# Smart_bot_V2_0.net
KiCad netlist of a schematic drawn in EAGLE
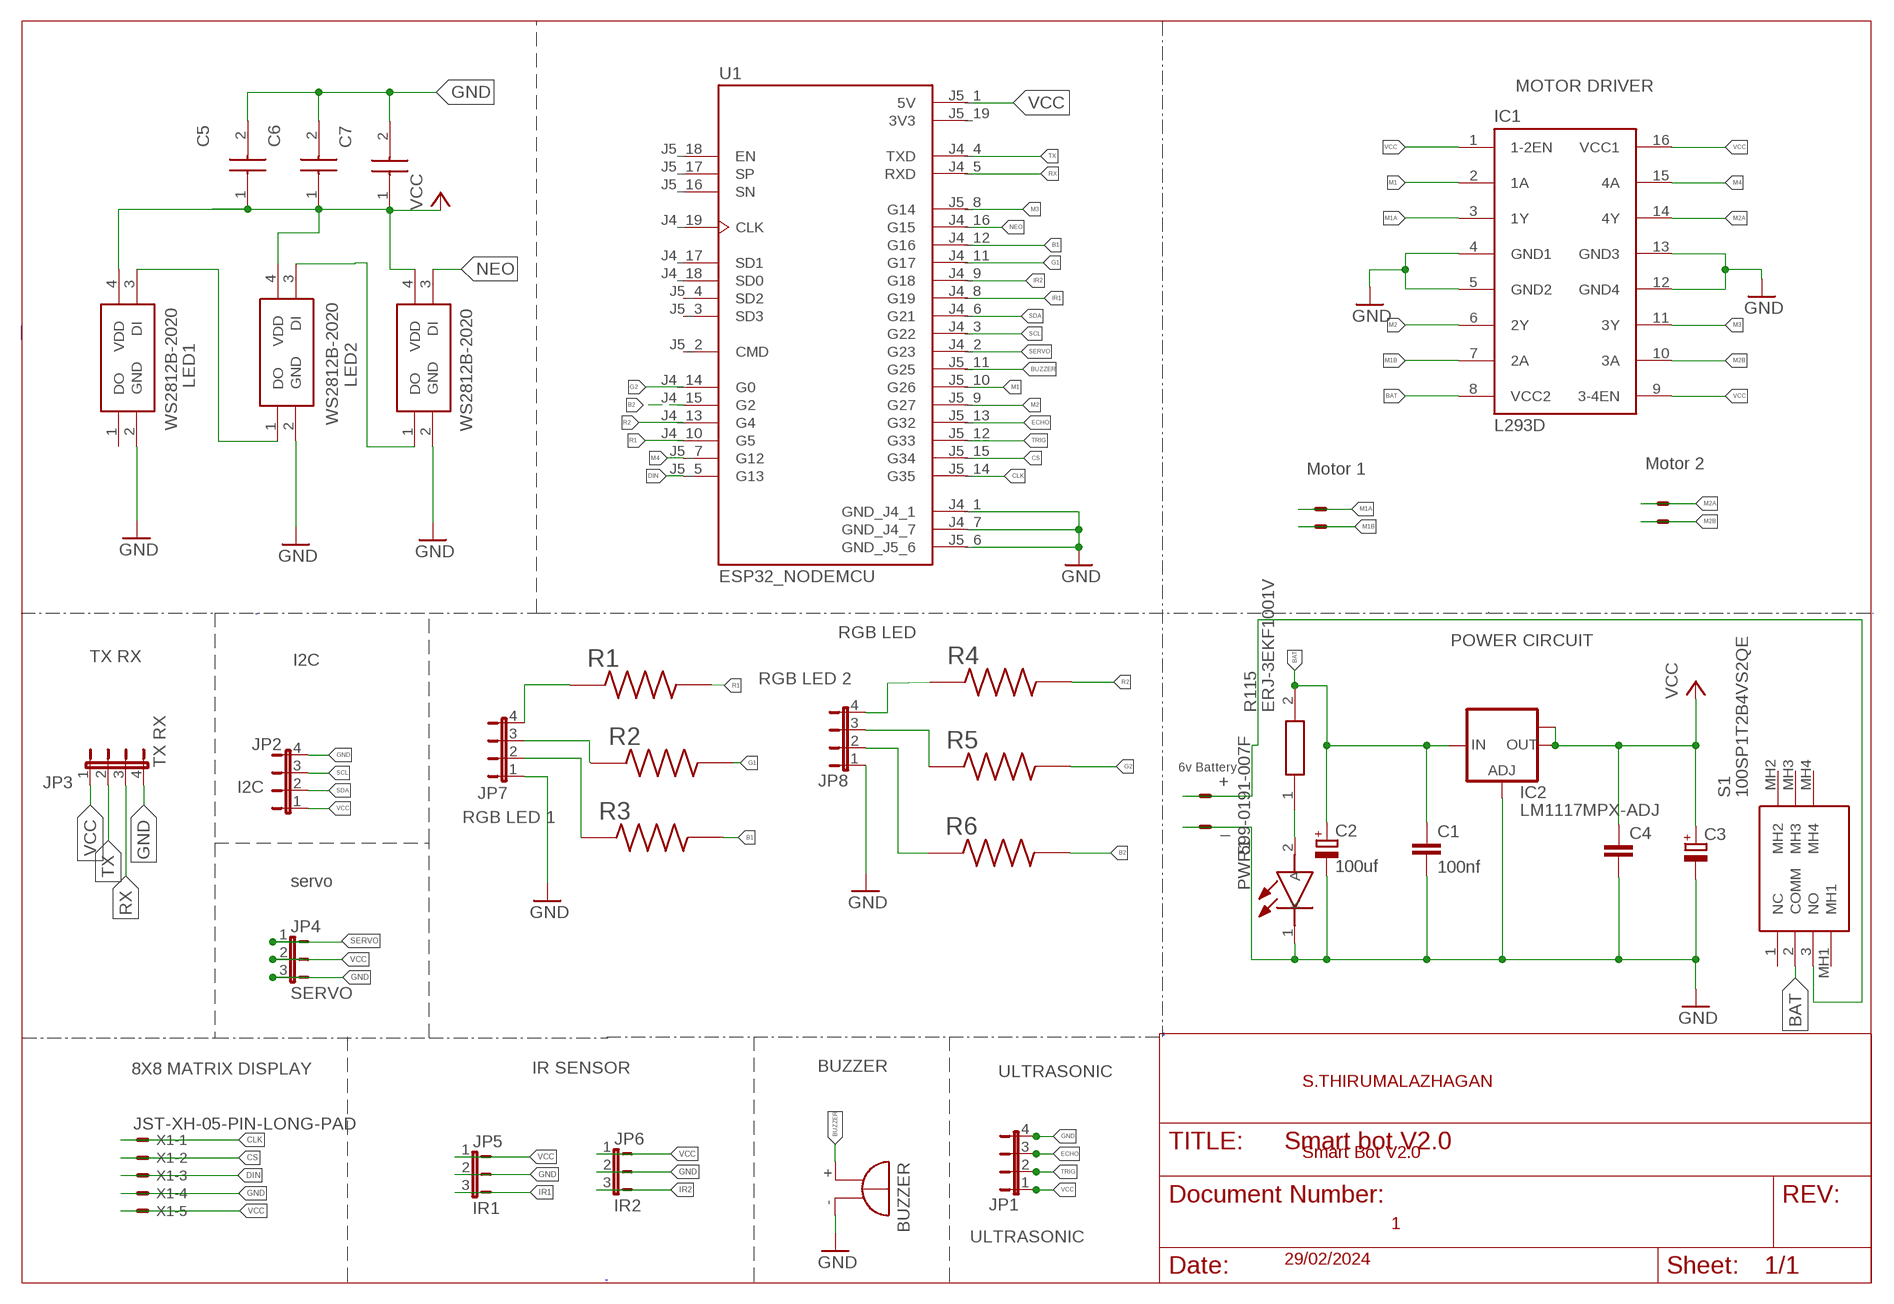
[diagram p0: schematic, sheet 1]

(export (version "E")
  (design (tool "Eeschema 10.0.6"))
  (components
    (comp (ref "6V")
      (value "JST-XH-02-PIN-LONG-PAD")
      (footprint "eagle-import:JST-XH-02-PACKAGE-LONG-PAD")
      (libsource (lib "eagle-import") (part "JST-XH-02-PIN-LONG-PAD"))
    )
    (comp (ref "BUZZER")
      (value "F/HMB")
      (footprint "eagle-import:F_HMB")
      (libsource (lib "eagle-import") (part "F/HMB"))
    )
    (comp (ref "C1")
      (value "100nf")
      (footprint "eagle-import:C1206")
      (libsource (lib "eagle-import") (part "C-EUC1206"))
    )
    (comp (ref "C2")
      (value "100uf")
      (footprint "eagle-import:SMC_B")
      (libsource (lib "eagle-import") (part "CPOL-EUSMCB"))
    )
    (comp (ref "C3")
      (value "CPOL-EUSMCB")
      (footprint "eagle-import:SMC_B")
      (libsource (lib "eagle-import") (part "CPOL-EUSMCB"))
    )
    (comp (ref "C4")
      (value "C-EUC1206")
      (footprint "eagle-import:C1206")
      (libsource (lib "eagle-import") (part "C-EUC1206"))
    )
    (comp (ref "C5")
      (value "C0805X102KMRECAUTO7210")
      (footprint "eagle-import:CAPC2012X98N")
      (fields (field (name "MOUSER_PART_NUMBER") "80-C0805X102KMREAULR"))
      (libsource (lib "eagle-import") (part "C0805X102KMRECAUTO7210"))
    )
    (comp (ref "C6")
      (value "C0805X102KMRECAUTO7210")
      (footprint "eagle-import:CAPC2012X98N")
      (fields (field (name "MOUSER_PART_NUMBER") "80-C0805X102KMREAULR"))
      (libsource (lib "eagle-import") (part "C0805X102KMRECAUTO7210"))
    )
    (comp (ref "C7")
      (value "C0805X102KMRECAUTO7210")
      (footprint "eagle-import:CAPC2012X98N")
      (fields (field (name "MOUSER_PART_NUMBER") "80-C0805X102KMREAULR"))
      (libsource (lib "eagle-import") (part "C0805X102KMRECAUTO7210"))
    )
    (comp (ref "IC1")
      (value "L293D")
      (footprint "eagle-import:DIL16")
      (libsource (lib "eagle-import") (part "L293D"))
    )
    (comp (ref "IC2")
      (value "LM1117MPX-ADJ")
      (footprint "eagle-import:SOT223")
      (libsource (lib "eagle-import") (part "LM1117MPX-ADJ"))
    )
    (comp (ref "JP1")
      (value "ULTRASONIC")
      (footprint "eagle-import:JP4")
      (libsource (lib "eagle-import") (part "JP4E"))
    )
    (comp (ref "JP2")
      (value "I2C")
      (footprint "eagle-import:JP4")
      (libsource (lib "eagle-import") (part "JP4E"))
    )
    (comp (ref "JP3")
      (value "TX RX")
      (footprint "eagle-import:JP4")
      (libsource (lib "eagle-import") (part "JP4E"))
    )
    (comp (ref "JP4")
      (value "SERVO")
      (footprint "eagle-import:JP2")
      (libsource (lib "eagle-import") (part "JP2E"))
    )
    (comp (ref "JP5")
      (value "IR1")
      (footprint "eagle-import:JP2")
      (libsource (lib "eagle-import") (part "JP2E"))
    )
    (comp (ref "JP6")
      (value "IR2")
      (footprint "eagle-import:JP2")
      (libsource (lib "eagle-import") (part "JP2E"))
    )
    (comp (ref "JP7")
      (value "RGB LED 1")
      (footprint "eagle-import:JP4")
      (libsource (lib "eagle-import") (part "JP4E"))
    )
    (comp (ref "JP8")
      (value "RGB LED 2")
      (footprint "eagle-import:JP4")
      (libsource (lib "eagle-import") (part "JP4E"))
    )
    (comp (ref "LED1")
      (value "WS2812B-2020")
      (footprint "eagle-import:WS2812B2020")
      (libsource (lib "eagle-import") (part "WS2812B-2020"))
    )
    (comp (ref "LED2")
      (value "WS2812B-2020")
      (footprint "eagle-import:WS2812B2020")
      (libsource (lib "eagle-import") (part "WS2812B-2020"))
    )
    (comp (ref "LED3")
      (value "WS2812B-2020")
      (footprint "eagle-import:WS2812B2020")
      (libsource (lib "eagle-import") (part "WS2812B-2020"))
    )
    (comp (ref "PWR1")
      (value "599-0191-007F")
      (footprint "eagle-import:LEDC2012X90N")
      (fields (field (name "MOUSER_PART_NUMBER") "645-599-0191-007F"))
      (libsource (lib "eagle-import") (part "599-0191-007F"))
    )
    (comp (ref "R1")
      (value "RR0306P-101-D")
      (footprint "eagle-import:RESC0603X26N")
      (fields (field (name "MF") "Susumu"))
      (libsource (lib "eagle-import") (part "RR0306P-101-D"))
    )
    (comp (ref "R2")
      (value "RR0306P-101-D")
      (footprint "eagle-import:RESC0603X26N")
      (fields (field (name "MF") "Susumu"))
      (libsource (lib "eagle-import") (part "RR0306P-101-D"))
    )
    (comp (ref "R3")
      (value "RR0306P-101-D")
      (footprint "eagle-import:RESC0603X26N")
      (fields (field (name "MF") "Susumu"))
      (libsource (lib "eagle-import") (part "RR0306P-101-D"))
    )
    (comp (ref "R4")
      (value "RR0306P-101-D")
      (footprint "eagle-import:RESC0603X26N")
      (fields (field (name "MF") "Susumu"))
      (libsource (lib "eagle-import") (part "RR0306P-101-D"))
    )
    (comp (ref "R5")
      (value "RR0306P-101-D")
      (footprint "eagle-import:RESC0603X26N")
      (fields (field (name "MF") "Susumu"))
      (libsource (lib "eagle-import") (part "RR0306P-101-D"))
    )
    (comp (ref "R6")
      (value "RR0306P-101-D")
      (footprint "eagle-import:RESC0603X26N")
      (fields (field (name "MF") "Susumu"))
      (libsource (lib "eagle-import") (part "RR0306P-101-D"))
    )
    (comp (ref "R115")
      (value "ERJ-3EKF1001V")
      (footprint "eagle-import:RESC1608X55N")
      (fields (field (name "MOUSER_PART_NUMBER") "667-ERJ-3EKF1001V"))
      (libsource (lib "eagle-import") (part "ERJ-3EKF1001V"))
    )
    (comp (ref "S1")
      (value "100SP1T2B4VS2QE")
      (footprint "eagle-import:100SP1T2B4VS2QE")
      (fields (field (name "MOUSER_PART_NUMBER") "612-100SP1T2B4VSQ"))
      (libsource (lib "eagle-import") (part "100SP1T2B4VS2QE"))
    )
    (comp (ref "U1")
      (value "ESP32_NODEMCU")
      (footprint "eagle-import:MODULE_ESP32_NODEMCU")
      (fields (field (name "MF") "AZ Delivery") (field (name "MP") "ESP32 NODEMCU"))
      (libsource (lib "eagle-import") (part "ESP32_NODEMCU"))
    )
    (comp (ref "X1")
      (value "JST-XH-05-PIN-LONG-PAD")
      (footprint "eagle-import:JST-XH-05-PACKAGE-LONG-PAD")
      (libsource (lib "eagle-import") (part "JST-XH-05-PIN-LONG-PAD"))
    )
    (comp (ref "X2")
      (value "JST-XH-02-PIN-LONG-PAD")
      (footprint "eagle-import:JST-XH-02-PACKAGE-LONG-PAD")
      (libsource (lib "eagle-import") (part "JST-XH-02-PIN-LONG-PAD"))
    )
    (comp (ref "X3")
      (value "JST-XH-02-PIN-LONG-PAD")
      (footprint "eagle-import:JST-XH-02-PACKAGE-LONG-PAD")
      (libsource (lib "eagle-import") (part "JST-XH-02-PIN-LONG-PAD"))
    )
  )
  (nets
    (net (code "1") (name "/3V3") (class "Default")
      (node (ref "U1") (pin "J5_19") (pinfunction "3V3_J5_19") (pintype "power_in"))
    )
    (net (code "2") (name "B1") (class "Default")
      (node (ref "R3") (pin "2") (pinfunction "2_2") (pintype "passive"))
      (node (ref "U1") (pin "J4_12") (pinfunction "G16_J4_12") (pintype "bidirectional"))
    )
    (net (code "3") (name "B2") (class "Default")
      (node (ref "R6") (pin "2") (pinfunction "2_2") (pintype "passive"))
      (node (ref "U1") (pin "J4_15") (pinfunction "G2_J4_15") (pintype "bidirectional"))
    )
    (net (code "4") (name "BAT") (class "Default")
      (node (ref "C1") (pin "1") (pinfunction "1_1") (pintype "passive"))
      (node (ref "C2") (pin "+") (pinfunction "+_+") (pintype "passive"))
      (node (ref "IC1") (pin "8") (pinfunction "VCC2_8") (pintype "power_in"))
      (node (ref "IC2") (pin "3") (pinfunction "IN_3") (pintype "input"))
      (node (ref "R115") (pin "2") (pinfunction "2_2") (pintype "bidirectional"))
      (node (ref "S1") (pin "2") (pinfunction "COMM_2") (pintype "bidirectional"))
    )
    (net (code "5") (name "BUZZER") (class "Default")
      (node (ref "BUZZER") (pin "+") (pinfunction "+_+") (pintype "passive"))
      (node (ref "U1") (pin "J5_11") (pinfunction "G25_J5_11") (pintype "bidirectional"))
    )
    (net (code "6") (name "CLK") (class "Default")
      (node (ref "U1") (pin "J5_14") (pinfunction "G35_J5_14") (pintype "bidirectional"))
      (node (ref "X1") (pin "1") (pinfunction "S_1") (pintype "passive"))
    )
    (net (code "7") (name "CS") (class "Default")
      (node (ref "U1") (pin "J5_15") (pinfunction "G34_J5_15") (pintype "bidirectional"))
      (node (ref "X1") (pin "2") (pinfunction "S_2") (pintype "passive"))
    )
    (net (code "8") (name "DIN") (class "Default")
      (node (ref "U1") (pin "J5_5") (pinfunction "G13_J5_5") (pintype "bidirectional"))
      (node (ref "X1") (pin "3") (pinfunction "S_3") (pintype "passive"))
    )
    (net (code "9") (name "ECHO") (class "Default")
      (node (ref "JP1") (pin "3") (pinfunction "3_3") (pintype "passive"))
      (node (ref "U1") (pin "J5_13") (pinfunction "G32_J5_13") (pintype "bidirectional"))
    )
    (net (code "10") (name "G1") (class "Default")
      (node (ref "R2") (pin "2") (pinfunction "2_2") (pintype "passive"))
      (node (ref "U1") (pin "J4_11") (pinfunction "G17_J4_11") (pintype "bidirectional"))
    )
    (net (code "11") (name "G2") (class "Default")
      (node (ref "R5") (pin "2") (pinfunction "2_2") (pintype "passive"))
      (node (ref "U1") (pin "J4_14") (pinfunction "G0_J4_14") (pintype "bidirectional"))
    )
    (net (code "12") (name "GND") (class "Default")
      (node (ref "6V") (pin "2") (pinfunction "S_2") (pintype "passive"))
      (node (ref "BUZZER") (pin "-") (pinfunction "-_-") (pintype "passive"))
      (node (ref "C1") (pin "2") (pinfunction "2_2") (pintype "passive"))
      (node (ref "C2") (pin "-") (pinfunction "-_-") (pintype "passive"))
      (node (ref "C3") (pin "-") (pinfunction "-_-") (pintype "passive"))
      (node (ref "C4") (pin "2") (pinfunction "2_2") (pintype "passive"))
      (node (ref "C5") (pin "2") (pinfunction "2_2") (pintype "bidirectional"))
      (node (ref "C6") (pin "2") (pinfunction "2_2") (pintype "bidirectional"))
      (node (ref "C7") (pin "2") (pinfunction "2_2") (pintype "bidirectional"))
      (node (ref "IC1") (pin "12") (pinfunction "GND4_12") (pintype "power_in"))
      (node (ref "IC1") (pin "13") (pinfunction "GND3_13") (pintype "power_in"))
      (node (ref "IC1") (pin "4") (pinfunction "GND1_4") (pintype "power_in"))
      (node (ref "IC1") (pin "5") (pinfunction "GND2_5") (pintype "power_in"))
      (node (ref "IC2") (pin "1") (pinfunction "ADJ_1") (pintype "input"))
      (node (ref "JP1") (pin "4") (pinfunction "4_4") (pintype "passive"))
      (node (ref "JP2") (pin "4") (pinfunction "4_4") (pintype "passive"))
      (node (ref "JP3") (pin "4") (pinfunction "4_4") (pintype "passive"))
      (node (ref "JP4") (pin "3") (pinfunction "3_3") (pintype "passive"))
      (node (ref "JP5") (pin "2") (pinfunction "2_2") (pintype "passive"))
      (node (ref "JP6") (pin "2") (pinfunction "2_2") (pintype "passive"))
      (node (ref "JP7") (pin "1") (pinfunction "1_1") (pintype "passive"))
      (node (ref "JP8") (pin "1") (pinfunction "1_1") (pintype "passive"))
      (node (ref "LED1") (pin "2") (pinfunction "GND_2") (pintype "bidirectional"))
      (node (ref "LED2") (pin "2") (pinfunction "GND_2") (pintype "bidirectional"))
      (node (ref "LED3") (pin "2") (pinfunction "GND_2") (pintype "bidirectional"))
      (node (ref "PWR1") (pin "1") (pinfunction "K_1") (pintype "bidirectional"))
      (node (ref "U1") (pin "J4_1") (pinfunction "GND_J4_1_J4_1") (pintype "power_in"))
      (node (ref "U1") (pin "J4_7") (pinfunction "GND_J4_7_J4_7") (pintype "power_in"))
      (node (ref "U1") (pin "J5_6") (pinfunction "GND_J5_6_J5_6") (pintype "power_in"))
      (node (ref "X1") (pin "4") (pinfunction "S_4") (pintype "passive"))
    )
    (net (code "13") (name "IR1") (class "Default")
      (node (ref "JP5") (pin "3") (pinfunction "3_3") (pintype "passive"))
      (node (ref "U1") (pin "J4_8") (pinfunction "G19_J4_8") (pintype "bidirectional"))
    )
    (net (code "14") (name "IR2") (class "Default")
      (node (ref "JP6") (pin "3") (pinfunction "3_3") (pintype "passive"))
      (node (ref "U1") (pin "J4_9") (pinfunction "G18_J4_9") (pintype "bidirectional"))
    )
    (net (code "15") (name "M1") (class "Default")
      (node (ref "IC1") (pin "2") (pinfunction "1A_2") (pintype "input"))
      (node (ref "U1") (pin "J5_10") (pinfunction "G26_J5_10") (pintype "bidirectional"))
    )
    (net (code "16") (name "M1A") (class "Default")
      (node (ref "IC1") (pin "3") (pinfunction "1Y_3") (pintype "output"))
      (node (ref "X2") (pin "1") (pinfunction "S_1") (pintype "passive"))
    )
    (net (code "17") (name "M1B") (class "Default")
      (node (ref "IC1") (pin "7") (pinfunction "2A_7") (pintype "input"))
      (node (ref "X2") (pin "2") (pinfunction "S_2") (pintype "passive"))
    )
    (net (code "18") (name "M2") (class "Default")
      (node (ref "IC1") (pin "6") (pinfunction "2Y_6") (pintype "output"))
      (node (ref "U1") (pin "J5_9") (pinfunction "G27_J5_9") (pintype "bidirectional"))
    )
    (net (code "19") (name "M2A") (class "Default")
      (node (ref "IC1") (pin "14") (pinfunction "4Y_14") (pintype "output"))
      (node (ref "X3") (pin "1") (pinfunction "S_1") (pintype "passive"))
    )
    (net (code "20") (name "M2B") (class "Default")
      (node (ref "IC1") (pin "10") (pinfunction "3A_10") (pintype "input"))
      (node (ref "X3") (pin "2") (pinfunction "S_2") (pintype "passive"))
    )
    (net (code "21") (name "M3") (class "Default")
      (node (ref "IC1") (pin "11") (pinfunction "3Y_11") (pintype "output"))
      (node (ref "U1") (pin "J5_8") (pinfunction "G14_J5_8") (pintype "bidirectional"))
    )
    (net (code "22") (name "M4") (class "Default")
      (node (ref "IC1") (pin "15") (pinfunction "4A_15") (pintype "input"))
      (node (ref "U1") (pin "J5_7") (pinfunction "G12_J5_7") (pintype "bidirectional"))
    )
    (net (code "23") (name "NEO") (class "Default")
      (node (ref "LED3") (pin "3") (pinfunction "DI_3") (pintype "bidirectional"))
      (node (ref "U1") (pin "J4_16") (pinfunction "G15_J4_16") (pintype "bidirectional"))
    )
    (net (code "24") (name "Net-(6VA-S)") (class "Default")
      (node (ref "6V") (pin "1") (pinfunction "S_1") (pintype "passive"))
      (node (ref "S1") (pin "3") (pinfunction "NO_3") (pintype "bidirectional"))
    )
    (net (code "25") (name "Net-(JP7-Pad2)") (class "Default")
      (node (ref "JP7") (pin "2") (pinfunction "2_2") (pintype "passive"))
      (node (ref "R3") (pin "1") (pinfunction "1_1") (pintype "passive"))
    )
    (net (code "26") (name "Net-(JP7-Pad3)") (class "Default")
      (node (ref "JP7") (pin "3") (pinfunction "3_3") (pintype "passive"))
      (node (ref "R2") (pin "1") (pinfunction "1_1") (pintype "passive"))
    )
    (net (code "27") (name "Net-(JP7-Pad4)") (class "Default")
      (node (ref "JP7") (pin "4") (pinfunction "4_4") (pintype "passive"))
      (node (ref "R1") (pin "1") (pinfunction "1_1") (pintype "passive"))
    )
    (net (code "28") (name "Net-(JP8-Pad2)") (class "Default")
      (node (ref "JP8") (pin "2") (pinfunction "2_2") (pintype "passive"))
      (node (ref "R6") (pin "1") (pinfunction "1_1") (pintype "passive"))
    )
    (net (code "29") (name "Net-(JP8-Pad3)") (class "Default")
      (node (ref "JP8") (pin "3") (pinfunction "3_3") (pintype "passive"))
      (node (ref "R5") (pin "1") (pinfunction "1_1") (pintype "passive"))
    )
    (net (code "30") (name "Net-(JP8-Pad4)") (class "Default")
      (node (ref "JP8") (pin "4") (pinfunction "4_4") (pintype "passive"))
      (node (ref "R4") (pin "1") (pinfunction "1_1") (pintype "passive"))
    )
    (net (code "31") (name "Net-(LED1-DI)") (class "Default")
      (node (ref "LED1") (pin "3") (pinfunction "DI_3") (pintype "bidirectional"))
      (node (ref "LED2") (pin "1") (pinfunction "DO_1") (pintype "bidirectional"))
    )
    (net (code "32") (name "Net-(LED2-DI)") (class "Default")
      (node (ref "LED2") (pin "3") (pinfunction "DI_3") (pintype "bidirectional"))
      (node (ref "LED3") (pin "1") (pinfunction "DO_1") (pintype "bidirectional"))
    )
    (net (code "33") (name "Net-(PWR1-A)") (class "Default")
      (node (ref "PWR1") (pin "2") (pinfunction "A_2") (pintype "bidirectional"))
      (node (ref "R115") (pin "1") (pinfunction "1_1") (pintype "bidirectional"))
    )
    (net (code "34") (name "R1") (class "Default")
      (node (ref "R1") (pin "2") (pinfunction "2_2") (pintype "passive"))
      (node (ref "U1") (pin "J4_10") (pinfunction "G5_J4_10") (pintype "bidirectional"))
    )
    (net (code "35") (name "R2") (class "Default")
      (node (ref "R4") (pin "2") (pinfunction "2_2") (pintype "passive"))
      (node (ref "U1") (pin "J4_13") (pinfunction "G4_J4_13") (pintype "bidirectional"))
    )
    (net (code "36") (name "RX") (class "Default")
      (node (ref "JP3") (pin "3") (pinfunction "3_3") (pintype "passive"))
      (node (ref "U1") (pin "J4_5") (pinfunction "RXD_J4_5") (pintype "input"))
    )
    (net (code "37") (name "SCL") (class "Default")
      (node (ref "JP2") (pin "3") (pinfunction "3_3") (pintype "passive"))
      (node (ref "U1") (pin "J4_3") (pinfunction "G22_J4_3") (pintype "bidirectional"))
    )
    (net (code "38") (name "SDA") (class "Default")
      (node (ref "JP2") (pin "2") (pinfunction "2_2") (pintype "passive"))
      (node (ref "U1") (pin "J4_6") (pinfunction "G21_J4_6") (pintype "bidirectional"))
    )
    (net (code "39") (name "SERVO") (class "Default")
      (node (ref "JP4") (pin "1") (pinfunction "1_1") (pintype "passive"))
      (node (ref "U1") (pin "J4_2") (pinfunction "G23_J4_2") (pintype "bidirectional"))
    )
    (net (code "40") (name "TRIG") (class "Default")
      (node (ref "JP1") (pin "2") (pinfunction "2_2") (pintype "passive"))
      (node (ref "U1") (pin "J5_12") (pinfunction "G33_J5_12") (pintype "bidirectional"))
    )
    (net (code "41") (name "TX") (class "Default")
      (node (ref "JP3") (pin "2") (pinfunction "2_2") (pintype "passive"))
      (node (ref "U1") (pin "J4_4") (pinfunction "TXD_J4_4") (pintype "output"))
    )
    (net (code "42") (name "VCC") (class "Default")
      (node (ref "C3") (pin "+") (pinfunction "+_+") (pintype "passive"))
      (node (ref "C4") (pin "1") (pinfunction "1_1") (pintype "passive"))
      (node (ref "C5") (pin "1") (pinfunction "1_1") (pintype "bidirectional"))
      (node (ref "C6") (pin "1") (pinfunction "1_1") (pintype "bidirectional"))
      (node (ref "C7") (pin "1") (pinfunction "1_1") (pintype "bidirectional"))
      (node (ref "IC1") (pin "1") (pinfunction "1-2EN_1") (pintype "input"))
      (node (ref "IC1") (pin "16") (pinfunction "VCC1_16") (pintype "power_in"))
      (node (ref "IC1") (pin "9") (pinfunction "3-4EN_9") (pintype "input"))
      (node (ref "IC2") (pin "2") (pinfunction "OUT_2") (pintype "passive"))
      (node (ref "IC2") (pin "TAB") (pinfunction "OUT1_TAB") (pintype "passive"))
      (node (ref "JP1") (pin "1") (pinfunction "1_1") (pintype "passive"))
      (node (ref "JP2") (pin "1") (pinfunction "1_1") (pintype "passive"))
      (node (ref "JP3") (pin "1") (pinfunction "1_1") (pintype "passive"))
      (node (ref "JP4") (pin "2") (pinfunction "2_2") (pintype "passive"))
      (node (ref "JP5") (pin "1") (pinfunction "1_1") (pintype "passive"))
      (node (ref "JP6") (pin "1") (pinfunction "1_1") (pintype "passive"))
      (node (ref "LED1") (pin "4") (pinfunction "VDD_4") (pintype "bidirectional"))
      (node (ref "LED2") (pin "4") (pinfunction "VDD_4") (pintype "bidirectional"))
      (node (ref "LED3") (pin "4") (pinfunction "VDD_4") (pintype "bidirectional"))
      (node (ref "U1") (pin "J5_1") (pinfunction "5V_J5_1") (pintype "power_in"))
      (node (ref "X1") (pin "5") (pinfunction "S_5") (pintype "passive"))
    )
    (net (code "43") (name "unconnected-(LED1-DO-Pad1)") (class "Default")
      (node (ref "LED1") (pin "1") (pinfunction "DO_1") (pintype "bidirectional"))
    )
    (net (code "44") (name "unconnected-(S1-NC-Pad1)") (class "Default")
      (node (ref "S1") (pin "1") (pinfunction "NC_1") (pintype "no_connect"))
    )
    (net (code "45") (name "unconnected-(S1-PadMH1)") (class "Default")
      (node (ref "S1") (pin "MH1") (pinfunction "MH1_MH1") (pintype "bidirectional"))
    )
    (net (code "46") (name "unconnected-(S1-PadMH2)") (class "Default")
      (node (ref "S1") (pin "MH2") (pinfunction "MH2_MH2") (pintype "bidirectional"))
    )
    (net (code "47") (name "unconnected-(S1-PadMH3)") (class "Default")
      (node (ref "S1") (pin "MH3") (pinfunction "MH3_MH3") (pintype "bidirectional"))
    )
    (net (code "48") (name "unconnected-(S1-PadMH4)") (class "Default")
      (node (ref "S1") (pin "MH4") (pinfunction "MH4_MH4") (pintype "bidirectional"))
    )
    (net (code "49") (name "unconnected-(U1-CLK-PadJ4_19)") (class "Default")
      (node (ref "U1") (pin "J4_19") (pinfunction "CLK_J4_19") (pintype "input"))
    )
    (net (code "50") (name "unconnected-(U1-CMD-PadJ5_2)") (class "Default")
      (node (ref "U1") (pin "J5_2") (pinfunction "CMD_J5_2") (pintype "bidirectional"))
    )
    (net (code "51") (name "unconnected-(U1-EN-PadJ5_18)") (class "Default")
      (node (ref "U1") (pin "J5_18") (pinfunction "EN_J5_18") (pintype "input"))
    )
    (net (code "52") (name "unconnected-(U1-SD0-PadJ4_18)") (class "Default")
      (node (ref "U1") (pin "J4_18") (pinfunction "SD0_J4_18") (pintype "bidirectional"))
    )
    (net (code "53") (name "unconnected-(U1-SD1-PadJ4_17)") (class "Default")
      (node (ref "U1") (pin "J4_17") (pinfunction "SD1_J4_17") (pintype "bidirectional"))
    )
    (net (code "54") (name "unconnected-(U1-SD2-PadJ5_4)") (class "Default")
      (node (ref "U1") (pin "J5_4") (pinfunction "SD2_J5_4") (pintype "bidirectional"))
    )
    (net (code "55") (name "unconnected-(U1-SD3-PadJ5_3)") (class "Default")
      (node (ref "U1") (pin "J5_3") (pinfunction "SD3_J5_3") (pintype "bidirectional"))
    )
    (net (code "56") (name "unconnected-(U1-SN-PadJ5_16)") (class "Default")
      (node (ref "U1") (pin "J5_16") (pinfunction "SN_J5_16") (pintype "input"))
    )
    (net (code "57") (name "unconnected-(U1-SP-PadJ5_17)") (class "Default")
      (node (ref "U1") (pin "J5_17") (pinfunction "SP_J5_17") (pintype "input"))
    )
  )
)
